# Pico_T61_Keyboard.net
KiCad netlist of a schematic drawn in EAGLE
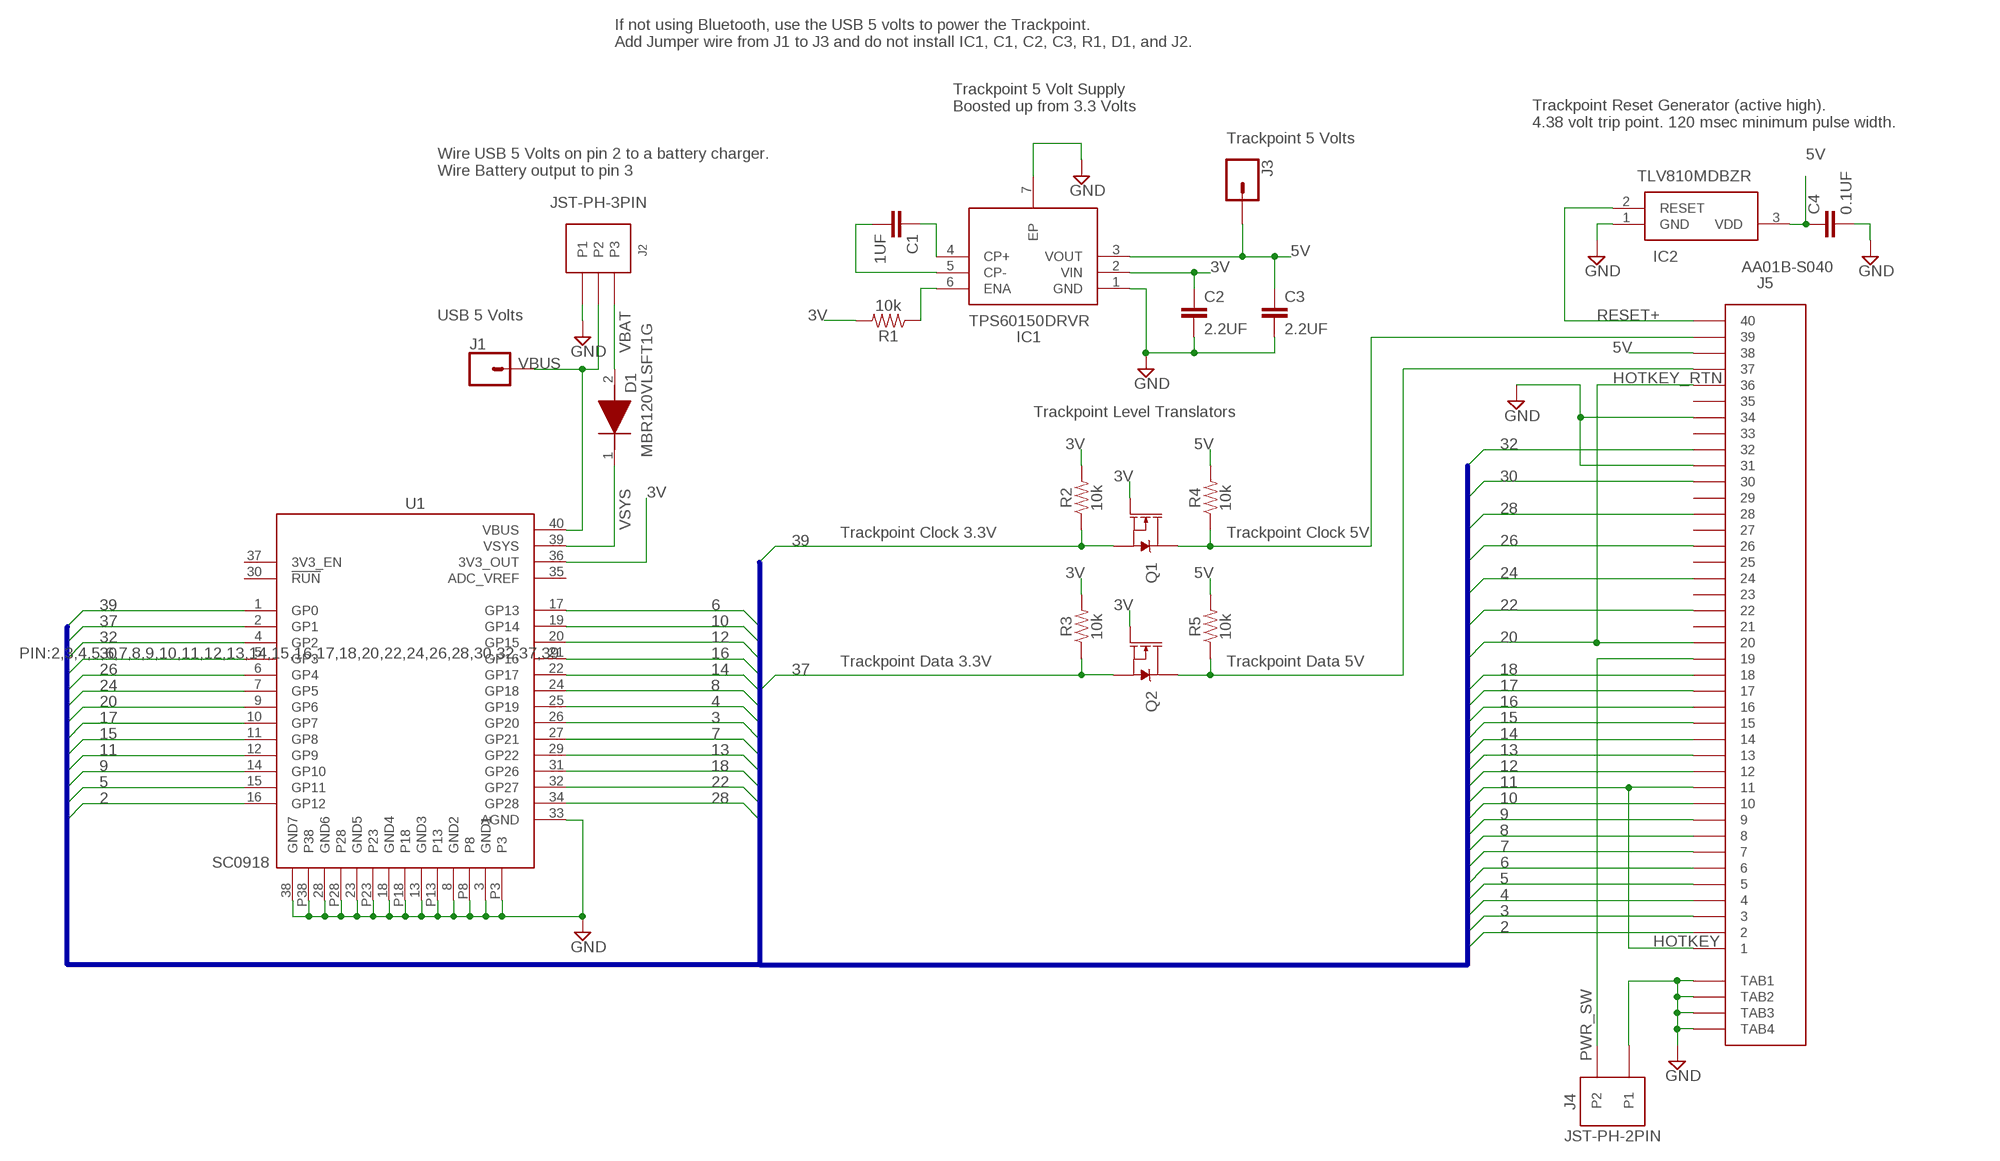
[diagram p0: schematic, sheet 1]

(export (version "E")
  (design (tool "Eeschema 10.0.6"))
  (components
    (comp (ref "C1")
      (value "1UF")
      (footprint "eagle-import:0603_CAP")
      (libsource (lib "eagle-import") (part "0603_CAP"))
    )
    (comp (ref "C2")
      (value "2.2UF")
      (footprint "eagle-import:0603_CAP")
      (libsource (lib "eagle-import") (part "0603_CAP"))
    )
    (comp (ref "C3")
      (value "2.2UF")
      (footprint "eagle-import:0603_CAP")
      (libsource (lib "eagle-import") (part "0603_CAP"))
    )
    (comp (ref "C4")
      (value "0.1UF")
      (footprint "eagle-import:0603_CAP")
      (libsource (lib "eagle-import") (part "0603_CAP"))
    )
    (comp (ref "D1")
      (value "MBR120VLSFT1G")
      (footprint "eagle-import:SODFL3616X98N")
      (fields (field (name "MOUSER_PART_NUMBER") "863-MBR120VLSFT1G"))
      (libsource (lib "eagle-import") (part "MBR120VLSFT1G"))
    )
    (comp (ref "IC1")
      (value "TPS60150DRVR")
      (footprint "eagle-import:SON65P200X200X80-7N")
      (fields (field (name "MOUSER_PART_NUMBER") "595-TPS60150DRVR"))
      (libsource (lib "eagle-import") (part "TPS60150DRVR"))
    )
    (comp (ref "IC2")
      (value "TLV810MDBZR")
      (footprint "eagle-import:SOT95P237X112-3N")
      (fields (field (name "MOUSER_PART_NUMBER") "595-TLV810MDBZR"))
      (libsource (lib "eagle-import") (part "TLV810MDBZR"))
    )
    (comp (ref "J1")
      (value "CONN_01")
      (footprint "eagle-import:1X01")
      (libsource (lib "eagle-import") (part "CONN_01"))
    )
    (comp (ref "J2")
      (value "JST-PH-3PIN")
      (footprint "eagle-import:JST-PH-3PIN")
      (libsource (lib "eagle-import") (part "JST-PH-3PIN"))
    )
    (comp (ref "J3")
      (value "CONN_01")
      (footprint "eagle-import:1X01")
      (libsource (lib "eagle-import") (part "CONN_01"))
    )
    (comp (ref "J4")
      (value "JST-PH-2PIN")
      (footprint "eagle-import:JST-PH-2PIN")
      (libsource (lib "eagle-import") (part "JST-PH-2PIN"))
    )
    (comp (ref "J5")
      (value "AA01B-S040")
      (footprint "eagle-import:WM6787_AA01B")
      (libsource (lib "eagle-import") (part "WM6787_A01B"))
    )
    (comp (ref "Q1")
      (value "220mA/50V/3.5Ω")
      (footprint "eagle-import:SOT23-3")
      (libsource (lib "eagle-import") (part "MOSFET-NCH-BSS138"))
    )
    (comp (ref "Q2")
      (value "220mA/50V/3.5Ω")
      (footprint "eagle-import:SOT23-3")
      (libsource (lib "eagle-import") (part "MOSFET-NCH-BSS138"))
    )
    (comp (ref "R1")
      (value "10k")
      (footprint "eagle-import:0603")
      (libsource (lib "eagle-import") (part "10KOHM-0603-1/10W-1%"))
    )
    (comp (ref "R2")
      (value "10k")
      (footprint "eagle-import:0603")
      (libsource (lib "eagle-import") (part "10KOHM-0603-1/10W-1%"))
    )
    (comp (ref "R3")
      (value "10k")
      (footprint "eagle-import:0603")
      (libsource (lib "eagle-import") (part "10KOHM-0603-1/10W-1%"))
    )
    (comp (ref "R4")
      (value "10k")
      (footprint "eagle-import:0603")
      (libsource (lib "eagle-import") (part "10KOHM-0603-1/10W-1%"))
    )
    (comp (ref "R5")
      (value "10k")
      (footprint "eagle-import:0603")
      (libsource (lib "eagle-import") (part "10KOHM-0603-1/10W-1%"))
    )
    (comp (ref "U1")
      (value "SC0918")
      (footprint "eagle-import:MODULE_SC0918")
      (fields (field (name "MF") "Raspberry Pi"))
      (libsource (lib "eagle-import") (part "SC0918"))
    )
  )
  (nets
    (net (code "2") (name "/2") (class "Default")
      (node (ref "J5") (pin "P$2") (pinfunction "2_P$2") (pintype "bidirectional"))
      (node (ref "U1") (pin "16") (pinfunction "GP12_16") (pintype "bidirectional"))
    )
    (net (code "3") (name "/3") (class "Default")
      (node (ref "J5") (pin "P$3") (pinfunction "3_P$3") (pintype "bidirectional"))
      (node (ref "U1") (pin "26") (pinfunction "GP20_26") (pintype "bidirectional"))
    )
    (net (code "4") (name "/3V") (class "Default")
      (node (ref "C2") (pin "1") (pinfunction "1_1") (pintype "passive"))
      (node (ref "IC1") (pin "2") (pinfunction "VIN_2") (pintype "bidirectional"))
      (node (ref "Q1") (pin "1") (pinfunction "G_1") (pintype "bidirectional"))
      (node (ref "Q2") (pin "1") (pinfunction "G_1") (pintype "bidirectional"))
      (node (ref "R1") (pin "2") (pinfunction "2_2") (pintype "passive"))
      (node (ref "R2") (pin "2") (pinfunction "2_2") (pintype "passive"))
      (node (ref "R3") (pin "2") (pinfunction "2_2") (pintype "passive"))
      (node (ref "U1") (pin "36") (pinfunction "3V3_OUT_36") (pintype "power_in"))
    )
    (net (code "5") (name "/4") (class "Default")
      (node (ref "J5") (pin "P$4") (pinfunction "4_P$4") (pintype "bidirectional"))
      (node (ref "U1") (pin "25") (pinfunction "GP19_25") (pintype "bidirectional"))
    )
    (net (code "6") (name "/5") (class "Default")
      (node (ref "J5") (pin "P$5") (pinfunction "5_P$5") (pintype "bidirectional"))
      (node (ref "U1") (pin "15") (pinfunction "GP11_15") (pintype "bidirectional"))
    )
    (net (code "7") (name "/5V") (class "Default")
      (node (ref "C3") (pin "1") (pinfunction "1_1") (pintype "passive"))
      (node (ref "C4") (pin "1") (pinfunction "1_1") (pintype "passive"))
      (node (ref "IC1") (pin "3") (pinfunction "VOUT_3") (pintype "bidirectional"))
      (node (ref "IC2") (pin "3") (pinfunction "VDD_3") (pintype "bidirectional"))
      (node (ref "J3") (pin "1") (pinfunction "1_1") (pintype "passive"))
      (node (ref "J5") (pin "P$38") (pinfunction "38_P$38") (pintype "bidirectional"))
      (node (ref "R4") (pin "2") (pinfunction "2_2") (pintype "passive"))
      (node (ref "R5") (pin "2") (pinfunction "2_2") (pintype "passive"))
    )
    (net (code "8") (name "/6") (class "Default")
      (node (ref "J5") (pin "P$6") (pinfunction "6_P$6") (pintype "bidirectional"))
      (node (ref "U1") (pin "17") (pinfunction "GP13_17") (pintype "bidirectional"))
    )
    (net (code "9") (name "/7") (class "Default")
      (node (ref "J5") (pin "P$7") (pinfunction "7_P$7") (pintype "bidirectional"))
      (node (ref "U1") (pin "27") (pinfunction "GP21_27") (pintype "bidirectional"))
    )
    (net (code "10") (name "/8") (class "Default")
      (node (ref "J5") (pin "P$8") (pinfunction "8_P$8") (pintype "bidirectional"))
      (node (ref "U1") (pin "24") (pinfunction "GP18_24") (pintype "bidirectional"))
    )
    (net (code "11") (name "/9") (class "Default")
      (node (ref "J5") (pin "P$9") (pinfunction "9_P$9") (pintype "bidirectional"))
      (node (ref "U1") (pin "14") (pinfunction "GP10_14") (pintype "bidirectional"))
    )
    (net (code "12") (name "/10") (class "Default")
      (node (ref "J5") (pin "P$10") (pinfunction "10_P$10") (pintype "bidirectional"))
      (node (ref "U1") (pin "19") (pinfunction "GP14_19") (pintype "bidirectional"))
    )
    (net (code "13") (name "/11") (class "Default")
      (node (ref "J5") (pin "P$1") (pinfunction "1_P$1") (pintype "bidirectional"))
      (node (ref "J5") (pin "P$11") (pinfunction "11_P$11") (pintype "bidirectional"))
      (node (ref "U1") (pin "12") (pinfunction "GP9_12") (pintype "bidirectional"))
    )
    (net (code "14") (name "/12") (class "Default")
      (node (ref "J5") (pin "P$12") (pinfunction "12_P$12") (pintype "bidirectional"))
      (node (ref "U1") (pin "20") (pinfunction "GP15_20") (pintype "bidirectional"))
    )
    (net (code "15") (name "/13") (class "Default")
      (node (ref "J5") (pin "P$13") (pinfunction "13_P$13") (pintype "bidirectional"))
      (node (ref "U1") (pin "29") (pinfunction "GP22_29") (pintype "bidirectional"))
    )
    (net (code "16") (name "/14") (class "Default")
      (node (ref "J5") (pin "P$14") (pinfunction "14_P$14") (pintype "bidirectional"))
      (node (ref "U1") (pin "22") (pinfunction "GP17_22") (pintype "bidirectional"))
    )
    (net (code "17") (name "/15") (class "Default")
      (node (ref "J5") (pin "P$15") (pinfunction "15_P$15") (pintype "bidirectional"))
      (node (ref "U1") (pin "11") (pinfunction "GP8_11") (pintype "bidirectional"))
    )
    (net (code "18") (name "/16") (class "Default")
      (node (ref "J5") (pin "P$16") (pinfunction "16_P$16") (pintype "bidirectional"))
      (node (ref "U1") (pin "21") (pinfunction "GP16_21") (pintype "bidirectional"))
    )
    (net (code "19") (name "/17") (class "Default")
      (node (ref "J5") (pin "P$17") (pinfunction "17_P$17") (pintype "bidirectional"))
      (node (ref "U1") (pin "10") (pinfunction "GP7_10") (pintype "bidirectional"))
    )
    (net (code "20") (name "/18") (class "Default")
      (node (ref "J5") (pin "P$18") (pinfunction "18_P$18") (pintype "bidirectional"))
      (node (ref "U1") (pin "31") (pinfunction "GP26_31") (pintype "bidirectional"))
    )
    (net (code "21") (name "/20") (class "Default")
      (node (ref "J5") (pin "P$20") (pinfunction "20_P$20") (pintype "bidirectional"))
      (node (ref "J5") (pin "P$36") (pinfunction "36_P$36") (pintype "bidirectional"))
      (node (ref "U1") (pin "9") (pinfunction "GP6_9") (pintype "bidirectional"))
    )
    (net (code "22") (name "/22") (class "Default")
      (node (ref "J5") (pin "P$22") (pinfunction "22_P$22") (pintype "bidirectional"))
      (node (ref "U1") (pin "32") (pinfunction "GP27_32") (pintype "bidirectional"))
    )
    (net (code "23") (name "/24") (class "Default")
      (node (ref "J5") (pin "P$24") (pinfunction "24_P$24") (pintype "bidirectional"))
      (node (ref "U1") (pin "7") (pinfunction "GP5_7") (pintype "bidirectional"))
    )
    (net (code "24") (name "/26") (class "Default")
      (node (ref "J5") (pin "P$26") (pinfunction "26_P$26") (pintype "bidirectional"))
      (node (ref "U1") (pin "6") (pinfunction "GP4_6") (pintype "bidirectional"))
    )
    (net (code "25") (name "/28") (class "Default")
      (node (ref "J5") (pin "P$28") (pinfunction "28_P$28") (pintype "bidirectional"))
      (node (ref "U1") (pin "34") (pinfunction "GP28_34") (pintype "bidirectional"))
    )
    (net (code "26") (name "/30") (class "Default")
      (node (ref "J5") (pin "P$30") (pinfunction "30_P$30") (pintype "bidirectional"))
      (node (ref "U1") (pin "5") (pinfunction "GP3_5") (pintype "bidirectional"))
    )
    (net (code "27") (name "/32") (class "Default")
      (node (ref "J5") (pin "P$32") (pinfunction "32_P$32") (pintype "bidirectional"))
      (node (ref "U1") (pin "4") (pinfunction "GP2_4") (pintype "bidirectional"))
    )
    (net (code "28") (name "/37") (class "Default")
      (node (ref "Q2") (pin "2") (pinfunction "S_2") (pintype "bidirectional"))
      (node (ref "R3") (pin "1") (pinfunction "1_1") (pintype "passive"))
      (node (ref "U1") (pin "2") (pinfunction "GP1_2") (pintype "bidirectional"))
    )
    (net (code "29") (name "/39") (class "Default")
      (node (ref "Q1") (pin "2") (pinfunction "S_2") (pintype "bidirectional"))
      (node (ref "R2") (pin "1") (pinfunction "1_1") (pintype "passive"))
      (node (ref "U1") (pin "1") (pinfunction "GP0_1") (pintype "bidirectional"))
    )
    (net (code "30") (name "/ADC_VREF") (class "Default")
      (node (ref "U1") (pin "35") (pinfunction "ADC_VREF_35") (pintype "power_in"))
    )
    (net (code "31") (name "/PWR_SW") (class "Default")
      (node (ref "J4") (pin "P$2") (pinfunction "P2_P$2") (pintype "bidirectional"))
      (node (ref "J5") (pin "P$19") (pinfunction "19_P$19") (pintype "bidirectional"))
    )
    (net (code "32") (name "/RESET+") (class "Default")
      (node (ref "IC2") (pin "2") (pinfunction "RESET_2") (pintype "bidirectional"))
      (node (ref "J5") (pin "P$40") (pinfunction "40_P$40") (pintype "bidirectional"))
    )
    (net (code "33") (name "/VBAT") (class "Default")
      (node (ref "D1") (pin "2") (pinfunction "A_2") (pintype "bidirectional"))
      (node (ref "J2") (pin "P$3") (pinfunction "P3_P$3") (pintype "bidirectional"))
    )
    (net (code "34") (name "/VBUS") (class "Default")
      (node (ref "J1") (pin "1") (pinfunction "1_1") (pintype "passive"))
      (node (ref "J2") (pin "P$2") (pinfunction "P2_P$2") (pintype "bidirectional"))
      (node (ref "U1") (pin "40") (pinfunction "VBUS_40") (pintype "power_in"))
    )
    (net (code "35") (name "/VSYS") (class "Default")
      (node (ref "D1") (pin "1") (pinfunction "K_1") (pintype "bidirectional"))
      (node (ref "U1") (pin "39") (pinfunction "VSYS_39") (pintype "power_in"))
    )
    (net (code "37") (name "GND") (class "Default")
      (node (ref "C2") (pin "2") (pinfunction "2_2") (pintype "passive"))
      (node (ref "C3") (pin "2") (pinfunction "2_2") (pintype "passive"))
      (node (ref "C4") (pin "2") (pinfunction "2_2") (pintype "passive"))
      (node (ref "IC1") (pin "1") (pinfunction "GND_1") (pintype "bidirectional"))
      (node (ref "IC1") (pin "7") (pinfunction "EP_7") (pintype "bidirectional"))
      (node (ref "IC2") (pin "1") (pinfunction "GND_1") (pintype "bidirectional"))
      (node (ref "J2") (pin "P$1") (pinfunction "P1_P$1") (pintype "bidirectional"))
      (node (ref "J4") (pin "P$1") (pinfunction "P1_P$1") (pintype "bidirectional"))
      (node (ref "J5") (pin "P$31") (pinfunction "31_P$31") (pintype "bidirectional"))
      (node (ref "J5") (pin "P$34") (pinfunction "34_P$34") (pintype "bidirectional"))
      (node (ref "J5") (pin "TAB1") (pinfunction "TAB1_TAB1") (pintype "bidirectional"))
      (node (ref "J5") (pin "TAB2") (pinfunction "TAB2_TAB2") (pintype "bidirectional"))
      (node (ref "J5") (pin "TAB3") (pinfunction "TAB3_TAB3") (pintype "bidirectional"))
      (node (ref "J5") (pin "TAB4") (pinfunction "TAB4_TAB4") (pintype "bidirectional"))
      (node (ref "U1") (pin "13") (pinfunction "GND3_13") (pintype "power_in"))
      (node (ref "U1") (pin "18") (pinfunction "GND4_18") (pintype "power_in"))
      (node (ref "U1") (pin "23") (pinfunction "GND5_23") (pintype "power_in"))
      (node (ref "U1") (pin "28") (pinfunction "GND6_28") (pintype "power_in"))
      (node (ref "U1") (pin "3") (pinfunction "GND1_3") (pintype "power_in"))
      (node (ref "U1") (pin "33") (pinfunction "AGND_33") (pintype "power_in"))
      (node (ref "U1") (pin "38") (pinfunction "GND7_38") (pintype "power_in"))
      (node (ref "U1") (pin "8") (pinfunction "GND2_8") (pintype "power_in"))
      (node (ref "U1") (pin "P13") (pinfunction "P13_P13") (pintype "power_in"))
      (node (ref "U1") (pin "P18") (pinfunction "P18_P18") (pintype "power_in"))
      (node (ref "U1") (pin "P23") (pinfunction "P23_P23") (pintype "power_in"))
      (node (ref "U1") (pin "P28") (pinfunction "P28_P28") (pintype "power_in"))
      (node (ref "U1") (pin "P3") (pinfunction "P3_P3") (pintype "power_in"))
      (node (ref "U1") (pin "P38") (pinfunction "P38_P38") (pintype "power_in"))
      (node (ref "U1") (pin "P8") (pinfunction "P8_P8") (pintype "power_in"))
    )
    (net (code "38") (name "Net-(IC1-CP+)") (class "Default")
      (node (ref "C1") (pin "1") (pinfunction "1_1") (pintype "passive"))
      (node (ref "IC1") (pin "4") (pinfunction "CP+_4") (pintype "bidirectional"))
    )
    (net (code "39") (name "Net-(IC1-CP-)") (class "Default")
      (node (ref "C1") (pin "2") (pinfunction "2_2") (pintype "passive"))
      (node (ref "IC1") (pin "5") (pinfunction "CP-_5") (pintype "bidirectional"))
    )
    (net (code "40") (name "Net-(IC1-ENA)") (class "Default")
      (node (ref "IC1") (pin "6") (pinfunction "ENA_6") (pintype "bidirectional"))
      (node (ref "R1") (pin "1") (pinfunction "1_1") (pintype "passive"))
    )
    (net (code "41") (name "Net-(J5-37)") (class "Default")
      (node (ref "J5") (pin "P$37") (pinfunction "37_P$37") (pintype "bidirectional"))
      (node (ref "Q2") (pin "3") (pinfunction "D_3") (pintype "bidirectional"))
      (node (ref "R5") (pin "1") (pinfunction "1_1") (pintype "passive"))
    )
    (net (code "42") (name "Net-(J5-39)") (class "Default")
      (node (ref "J5") (pin "P$39") (pinfunction "39_P$39") (pintype "bidirectional"))
      (node (ref "Q1") (pin "3") (pinfunction "D_3") (pintype "bidirectional"))
      (node (ref "R4") (pin "1") (pinfunction "1_1") (pintype "passive"))
    )
    (net (code "43") (name "unconnected-(J5-21-PadP$21)") (class "Default")
      (node (ref "J5") (pin "P$21") (pinfunction "21_P$21") (pintype "bidirectional"))
    )
    (net (code "44") (name "unconnected-(J5-23-PadP$23)") (class "Default")
      (node (ref "J5") (pin "P$23") (pinfunction "23_P$23") (pintype "bidirectional"))
    )
    (net (code "45") (name "unconnected-(J5-25-PadP$25)") (class "Default")
      (node (ref "J5") (pin "P$25") (pinfunction "25_P$25") (pintype "bidirectional"))
    )
    (net (code "46") (name "unconnected-(J5-27-PadP$27)") (class "Default")
      (node (ref "J5") (pin "P$27") (pinfunction "27_P$27") (pintype "bidirectional"))
    )
    (net (code "47") (name "unconnected-(J5-29-PadP$29)") (class "Default")
      (node (ref "J5") (pin "P$29") (pinfunction "29_P$29") (pintype "bidirectional"))
    )
    (net (code "48") (name "unconnected-(J5-33-PadP$33)") (class "Default")
      (node (ref "J5") (pin "P$33") (pinfunction "33_P$33") (pintype "bidirectional"))
    )
    (net (code "49") (name "unconnected-(J5-35-PadP$35)") (class "Default")
      (node (ref "J5") (pin "P$35") (pinfunction "35_P$35") (pintype "bidirectional"))
    )
    (net (code "50") (name "unconnected-(U1-3V3_EN-Pad37)") (class "Default")
      (node (ref "U1") (pin "37") (pinfunction "3V3_EN_37") (pintype "input"))
    )
    (net (code "51") (name "unconnected-(U1-~{RUN}-Pad30)") (class "Default")
      (node (ref "U1") (pin "30") (pinfunction "~{RUN}_30") (pintype "input"))
    )
  )
)
